# projetw2.net
KiCad netlist of a schematic drawn in EAGLE
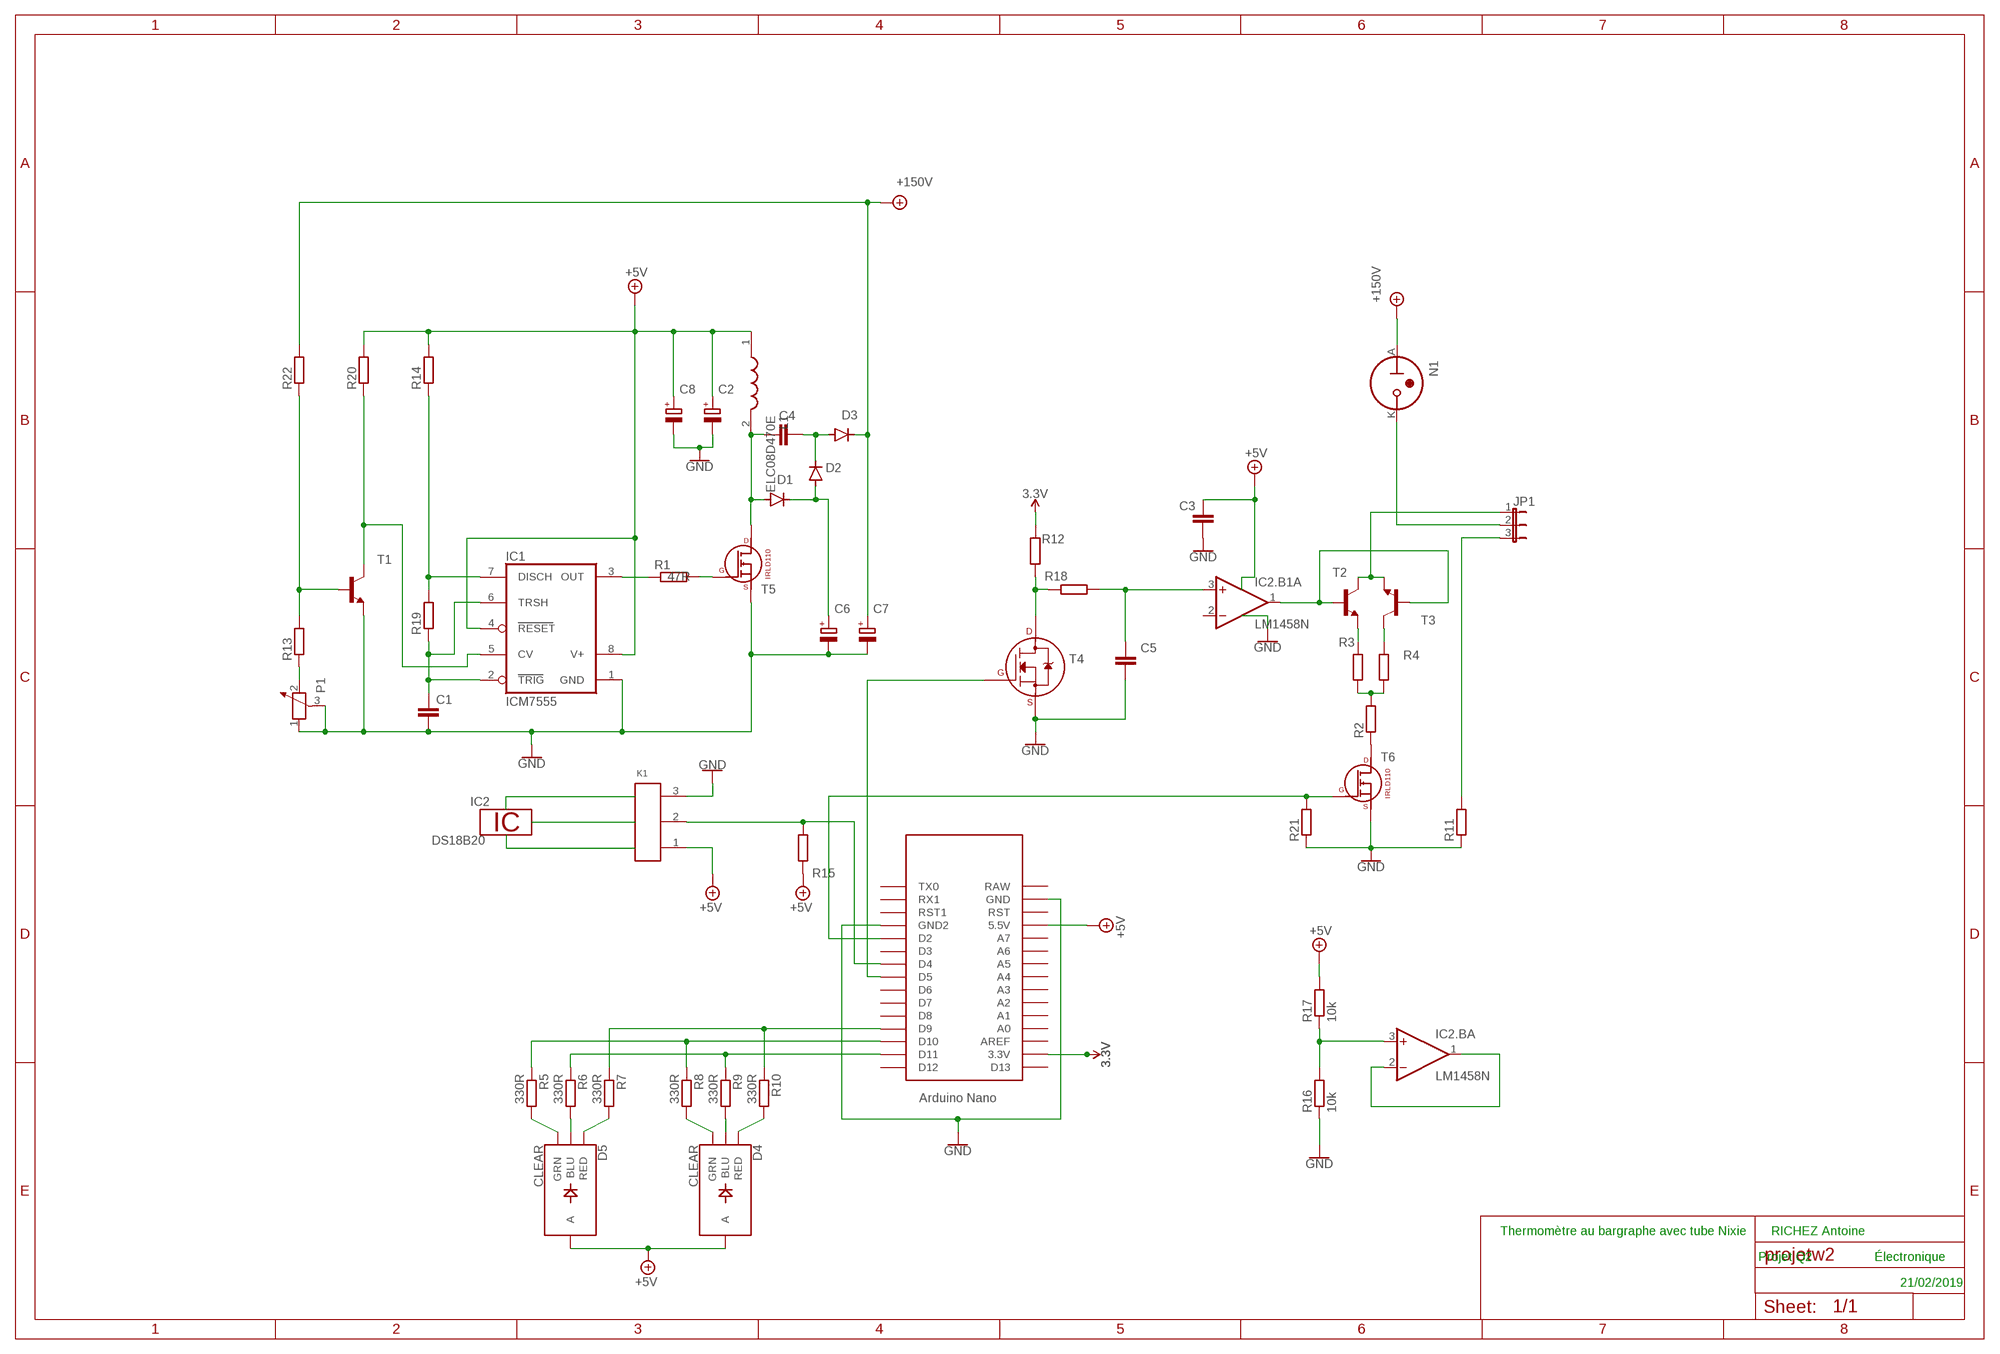
[diagram p0: schematic, sheet 1]

(export (version "E")
  (design (tool "Eeschema 10.0.6"))
  (components
    (comp (ref "C1")
      (value "C-EU025-024X044")
      (footprint "eagle-import:C025-024X044")
      (libsource (lib "eagle-import") (part "C-EU025-024X044"))
    )
    (comp (ref "C2")
      (value "CPOL-EUE2,5-6E")
      (footprint "eagle-import:E2,5-6E")
      (libsource (lib "eagle-import") (part "CPOL-EUE2,5-6E"))
    )
    (comp (ref "C3")
      (value "C-EU025-030X050")
      (footprint "eagle-import:C025-030X050")
      (libsource (lib "eagle-import") (part "C-EU025-030X050"))
    )
    (comp (ref "C4")
      (value "C-EU025-030X050")
      (footprint "eagle-import:C025-030X050")
      (libsource (lib "eagle-import") (part "C-EU025-030X050"))
    )
    (comp (ref "C5")
      (value "C-EU025-030X050")
      (footprint "eagle-import:C025-030X050")
      (libsource (lib "eagle-import") (part "C-EU025-030X050"))
    )
    (comp (ref "C6")
      (value "CPOL-EUE2,5-6E")
      (footprint "eagle-import:E2,5-6E")
      (libsource (lib "eagle-import") (part "CPOL-EUE2,5-6E"))
    )
    (comp (ref "C7")
      (value "CPOL-EUE2,5-6E")
      (footprint "eagle-import:E2,5-6E")
      (libsource (lib "eagle-import") (part "CPOL-EUE2,5-6E"))
    )
    (comp (ref "C8")
      (value "CPOL-EUE2,5-6E")
      (footprint "eagle-import:E2,5-6E")
      (libsource (lib "eagle-import") (part "CPOL-EUE2,5-6E"))
    )
    (comp (ref "D1")
      (value "MUR150RL")
      (footprint "eagle-import:DO41-10")
      (libsource (lib "eagle-import") (part "MUR150RL"))
    )
    (comp (ref "D2")
      (value "MUR150RL")
      (footprint "eagle-import:DO41-10")
      (libsource (lib "eagle-import") (part "MUR150RL"))
    )
    (comp (ref "D3")
      (value "MUR150RL")
      (footprint "eagle-import:DO41-10")
      (libsource (lib "eagle-import") (part "MUR150RL"))
    )
    (comp (ref "D4")
      (value "CLEAR")
      (footprint "eagle-import:LED-RGB-THRU")
      (libsource (lib "eagle-import") (part "LED-RGB-CACLEAR"))
    )
    (comp (ref "D5")
      (value "CLEAR")
      (footprint "eagle-import:LED-RGB-THRU")
      (libsource (lib "eagle-import") (part "LED-RGB-CACLEAR"))
    )
    (comp (ref "IC1")
      (value "ICM7555")
      (footprint "eagle-import:DIL08")
      (fields (field (name "MF") "MAXIM") (field (name "MPN") "ICM7555IPA+"))
      (libsource (lib "eagle-import") (part "ICM7555"))
    )
    (comp (ref "IC2")
      (value "DS18B20")
      (footprint "eagle-import:TO92-")
      (libsource (lib "eagle-import") (part "DS18B20"))
    )
    (comp (ref "IC2.B")
      (value "LM1458N")
      (footprint "eagle-import:DIL08")
      (libsource (lib "eagle-import") (part "1458NLM"))
    )
    (comp (ref "IC2.B1")
      (value "LM1458N")
      (footprint "eagle-import:DIL08")
      (libsource (lib "eagle-import") (part "1458NLM"))
    )
    (comp (ref "JP1")
      (value "JP2E")
      (footprint "eagle-import:JP2")
      (libsource (lib "eagle-import") (part "JP2E"))
    )
    (comp (ref "K1")
      (value "61900319521")
      (footprint "eagle-import:61900319521")
      (libsource (lib "eagle-import") (part "61900319521"))
    )
    (comp (ref "L1")
      (value "ELC08D470E")
      (footprint "eagle-import:ELC08D")
      (fields (field (name "MOUSER_PART_NUMBER") "2335178P"))
      (libsource (lib "eagle-import") (part "ELC08D470E"))
    )
    (comp (ref "N1")
      (value "IN-9")
      (footprint "eagle-import:IN-9")
      (libsource (lib "eagle-import") (part "IN-9"))
    )
    (comp (ref "P1")
      (value "POTENTIOMETER_PT-10")
      (footprint "eagle-import:PT-10")
      (libsource (lib "eagle-import") (part "POTENTIOMETER_PT-10"))
    )
    (comp (ref "R1")
      (value "47R")
      (footprint "eagle-import:0204_7")
      (libsource (lib "eagle-import") (part "R-EU_0204/7"))
    )
    (comp (ref "R2")
      (value "R-EU_0204/7")
      (footprint "eagle-import:0204_7")
      (libsource (lib "eagle-import") (part "R-EU_0204/7"))
    )
    (comp (ref "R3")
      (value "R-EU_0207/2V")
      (footprint "eagle-import:0207_2V")
      (libsource (lib "eagle-import") (part "R-EU_0207/2V"))
    )
    (comp (ref "R4")
      (value "R-EU_0207/2V")
      (footprint "eagle-import:0207_2V")
      (libsource (lib "eagle-import") (part "R-EU_0207/2V"))
    )
    (comp (ref "R5")
      (value "330R")
      (footprint "eagle-import:0204V")
      (libsource (lib "eagle-import") (part "R-EU_0204/2V"))
    )
    (comp (ref "R6")
      (value "330R")
      (footprint "eagle-import:0204V")
      (libsource (lib "eagle-import") (part "R-EU_0204/2V"))
    )
    (comp (ref "R7")
      (value "330R")
      (footprint "eagle-import:0204V")
      (libsource (lib "eagle-import") (part "R-EU_0204/2V"))
    )
    (comp (ref "R8")
      (value "330R")
      (footprint "eagle-import:0204V")
      (libsource (lib "eagle-import") (part "R-EU_0204/2V"))
    )
    (comp (ref "R9")
      (value "330R")
      (footprint "eagle-import:0204V")
      (libsource (lib "eagle-import") (part "R-EU_0204/2V"))
    )
    (comp (ref "R10")
      (value "330R")
      (footprint "eagle-import:0204V")
      (libsource (lib "eagle-import") (part "R-EU_0204/2V"))
    )
    (comp (ref "R11")
      (value "R-EU_0204/7")
      (footprint "eagle-import:0204_7")
      (libsource (lib "eagle-import") (part "R-EU_0204/7"))
    )
    (comp (ref "R12")
      (value "R-EU_0207/2V")
      (footprint "eagle-import:0207_2V")
      (libsource (lib "eagle-import") (part "R-EU_0207/2V"))
    )
    (comp (ref "R13")
      (value "R-EU_0207/2V")
      (footprint "eagle-import:0207_2V")
      (libsource (lib "eagle-import") (part "R-EU_0207/2V"))
    )
    (comp (ref "R14")
      (value "R-EU_0207/2V")
      (footprint "eagle-import:0207_2V")
      (libsource (lib "eagle-import") (part "R-EU_0207/2V"))
    )
    (comp (ref "R15")
      (value "R-EU_0204/7")
      (footprint "eagle-import:0204_7")
      (libsource (lib "eagle-import") (part "R-EU_0204/7"))
    )
    (comp (ref "R16")
      (value "10k")
      (footprint "eagle-import:0204V")
      (libsource (lib "eagle-import") (part "R-EU_0204/2V"))
    )
    (comp (ref "R17")
      (value "10k")
      (footprint "eagle-import:0204V")
      (libsource (lib "eagle-import") (part "R-EU_0204/2V"))
    )
    (comp (ref "R18")
      (value "R-EU_0207/2V")
      (footprint "eagle-import:0207_2V")
      (libsource (lib "eagle-import") (part "R-EU_0207/2V"))
    )
    (comp (ref "R19")
      (value "R-EU_0207/2V")
      (footprint "eagle-import:0207_2V")
      (libsource (lib "eagle-import") (part "R-EU_0207/2V"))
    )
    (comp (ref "R20")
      (value "R-EU_0207/2V")
      (footprint "eagle-import:0207_2V")
      (libsource (lib "eagle-import") (part "R-EU_0207/2V"))
    )
    (comp (ref "R21")
      (value "R-EU_0204/7")
      (footprint "eagle-import:0204_7")
      (libsource (lib "eagle-import") (part "R-EU_0204/7"))
    )
    (comp (ref "R22")
      (value "R-EU_0207/2V")
      (footprint "eagle-import:0207_2V")
      (libsource (lib "eagle-import") (part "R-EU_0207/2V"))
    )
    (comp (ref "T1")
      (value "BC547B-NPN-TO92-CBE")
      (footprint "eagle-import:TO92-CBE")
      (libsource (lib "eagle-import") (part "-NPN-TO92-CBEBC547B"))
    )
    (comp (ref "T2")
      (value "MPSA42-NPN-TO92-EBC")
      (footprint "eagle-import:TO92-EBC")
      (libsource (lib "eagle-import") (part "-NPN-TO92-EBCMPSA42"))
    )
    (comp (ref "T3")
      (value "MPSA42-NPN-TO92-EBC")
      (footprint "eagle-import:TO92-EBC")
      (libsource (lib "eagle-import") (part "-NPN-TO92-EBCMPSA42"))
    )
    (comp (ref "T4")
      (value "2N7000_TO92")
      (footprint "eagle-import:TO-92")
      (libsource (lib "eagle-import") (part "2N700_TO920"))
    )
    (comp (ref "T5")
      (value "-IRLD")
      (footprint "eagle-import:IRLD110")
      (libsource (lib "eagle-import") (part "-IRLD"))
    )
    (comp (ref "T6")
      (value "-IRLD")
      (footprint "eagle-import:IRLD110")
      (libsource (lib "eagle-import") (part "-IRLD"))
    )
    (comp (ref "U$1")
      (value "NANO")
      (footprint "eagle-import:NANO")
      (libsource (lib "eagle-import") (part "NANO"))
    )
  )
  (nets
    (net (code "1") (name "+150V") (class "Default")
      (node (ref "C2") (pin "+") (pinfunction "+_+") (pintype "passive"))
      (node (ref "C3") (pin "1") (pinfunction "1_1") (pintype "passive"))
      (node (ref "C7") (pin "+") (pinfunction "+_+") (pintype "passive"))
      (node (ref "C8") (pin "+") (pinfunction "+_+") (pintype "passive"))
      (node (ref "D3") (pin "C") (pinfunction "C_C") (pintype "passive"))
      (node (ref "D4") (pin "2") (pinfunction "A_2") (pintype "bidirectional"))
      (node (ref "D5") (pin "2") (pinfunction "A_2") (pintype "bidirectional"))
      (node (ref "IC1") (pin "4") (pinfunction "RESET_4") (pintype "input"))
      (node (ref "IC1") (pin "8") (pinfunction "V+_8") (pintype "power_in"))
      (node (ref "K1") (pin "1") (pinfunction "3_1") (pintype "passive"))
      (node (ref "L1") (pin "1") (pinfunction "1_1") (pintype "bidirectional"))
      (node (ref "N1") (pin "A") (pinfunction "A_A") (pintype "bidirectional"))
      (node (ref "R14") (pin "2") (pinfunction "2_2") (pintype "passive"))
      (node (ref "R15") (pin "1") (pinfunction "1_1") (pintype "passive"))
      (node (ref "R17") (pin "2") (pinfunction "2_2") (pintype "passive"))
      (node (ref "R20") (pin "2") (pinfunction "2_2") (pintype "passive"))
      (node (ref "R22") (pin "2") (pinfunction "2_2") (pintype "passive"))
      (node (ref "U$1") (pin "5V") (pinfunction "5.5V_5V") (pintype "bidirectional"))
    )
    (net (code "2") (name "3.3V") (class "Default")
      (node (ref "R12") (pin "1") (pinfunction "1_1") (pintype "passive"))
      (node (ref "U$1") (pin "3.3V") (pinfunction "3.3V_3.3V") (pintype "bidirectional"))
    )
    (net (code "3") (name "GND") (class "Default")
      (node (ref "C1") (pin "2") (pinfunction "2_2") (pintype "passive"))
      (node (ref "C2") (pin "-") (pinfunction "-_-") (pintype "passive"))
      (node (ref "C3") (pin "2") (pinfunction "2_2") (pintype "passive"))
      (node (ref "C5") (pin "2") (pinfunction "2_2") (pintype "passive"))
      (node (ref "C6") (pin "-") (pinfunction "-_-") (pintype "passive"))
      (node (ref "C7") (pin "-") (pinfunction "-_-") (pintype "passive"))
      (node (ref "C8") (pin "-") (pinfunction "-_-") (pintype "passive"))
      (node (ref "IC1") (pin "1") (pinfunction "GND_1") (pintype "power_in"))
      (node (ref "K1") (pin "3") (pinfunction "1_3") (pintype "passive"))
      (node (ref "P1") (pin "1") (pinfunction "1_1") (pintype "passive"))
      (node (ref "P1") (pin "3") (pinfunction "3_3") (pintype "passive"))
      (node (ref "R11") (pin "1") (pinfunction "1_1") (pintype "passive"))
      (node (ref "R16") (pin "1") (pinfunction "1_1") (pintype "passive"))
      (node (ref "R21") (pin "1") (pinfunction "1_1") (pintype "passive"))
      (node (ref "T1") (pin "E") (pinfunction "E_E") (pintype "passive"))
      (node (ref "T4") (pin "1") (pinfunction "S_1") (pintype "bidirectional"))
      (node (ref "T5") (pin "SOURCE") (pinfunction "SOURCE_SOURCE") (pintype "passive"))
      (node (ref "T6") (pin "SOURCE") (pinfunction "SOURCE_SOURCE") (pintype "passive"))
      (node (ref "U$1") (pin "GND") (pinfunction "GND_GND") (pintype "bidirectional"))
      (node (ref "U$1") (pin "GND1") (pinfunction "GND2_GND1") (pintype "bidirectional"))
    )
    (net (code "4") (name "Net-(C4-Pad2)") (class "Default")
      (node (ref "C4") (pin "2") (pinfunction "2_2") (pintype "passive"))
      (node (ref "D2") (pin "C") (pinfunction "C_C") (pintype "passive"))
      (node (ref "D3") (pin "A") (pinfunction "A_A") (pintype "passive"))
    )
    (net (code "5") (name "Net-(C6-Pad+)") (class "Default")
      (node (ref "C6") (pin "+") (pinfunction "+_+") (pintype "passive"))
      (node (ref "D1") (pin "C") (pinfunction "C_C") (pintype "passive"))
      (node (ref "D2") (pin "A") (pinfunction "A_A") (pintype "passive"))
    )
    (net (code "6") (name "Net-(D4-BLU)") (class "Default")
      (node (ref "D4") (pin "4") (pinfunction "BLU_4") (pintype "bidirectional"))
      (node (ref "R9") (pin "2") (pinfunction "2_2") (pintype "passive"))
    )
    (net (code "7") (name "Net-(D4-GRN)") (class "Default")
      (node (ref "D4") (pin "3") (pinfunction "GRN_3") (pintype "bidirectional"))
      (node (ref "R8") (pin "2") (pinfunction "2_2") (pintype "passive"))
    )
    (net (code "8") (name "Net-(D4-RED)") (class "Default")
      (node (ref "D4") (pin "1") (pinfunction "RED_1") (pintype "bidirectional"))
      (node (ref "R10") (pin "2") (pinfunction "2_2") (pintype "passive"))
    )
    (net (code "9") (name "Net-(D5-BLU)") (class "Default")
      (node (ref "D5") (pin "4") (pinfunction "BLU_4") (pintype "bidirectional"))
      (node (ref "R6") (pin "2") (pinfunction "2_2") (pintype "passive"))
    )
    (net (code "10") (name "Net-(D5-GRN)") (class "Default")
      (node (ref "D5") (pin "3") (pinfunction "GRN_3") (pintype "bidirectional"))
      (node (ref "R5") (pin "2") (pinfunction "2_2") (pintype "passive"))
    )
    (net (code "11") (name "Net-(D5-RED)") (class "Default")
      (node (ref "D5") (pin "1") (pinfunction "RED_1") (pintype "bidirectional"))
      (node (ref "R7") (pin "2") (pinfunction "2_2") (pintype "passive"))
    )
    (net (code "12") (name "Net-(IC1-CV)") (class "Default")
      (node (ref "IC1") (pin "5") (pinfunction "CV_5") (pintype "passive"))
      (node (ref "R20") (pin "1") (pinfunction "1_1") (pintype "passive"))
      (node (ref "T1") (pin "C") (pinfunction "C_C") (pintype "passive"))
    )
    (net (code "13") (name "Net-(IC1-DISCH)") (class "Default")
      (node (ref "IC1") (pin "7") (pinfunction "DISCH_7") (pintype "input"))
      (node (ref "R14") (pin "1") (pinfunction "1_1") (pintype "passive"))
      (node (ref "R19") (pin "2") (pinfunction "2_2") (pintype "passive"))
    )
    (net (code "14") (name "Net-(IC1-OUT)") (class "Default")
      (node (ref "IC1") (pin "3") (pinfunction "OUT_3") (pintype "output"))
      (node (ref "R1") (pin "1") (pinfunction "1_1") (pintype "passive"))
    )
    (net (code "15") (name "Net-(IC1-TRIG)") (class "Default")
      (node (ref "C1") (pin "1") (pinfunction "1_1") (pintype "passive"))
      (node (ref "IC1") (pin "2") (pinfunction "TRIG_2") (pintype "bidirectional"))
      (node (ref "IC1") (pin "6") (pinfunction "TRSH_6") (pintype "input"))
      (node (ref "R19") (pin "1") (pinfunction "1_1") (pintype "passive"))
    )
    (net (code "16") (name "Net-(IC2.B1A-+IN)") (class "Default")
      (node (ref "C5") (pin "1") (pinfunction "1_1") (pintype "passive"))
      (node (ref "IC2.B1") (pin "3") (pinfunction "+IN_3") (pintype "input"))
      (node (ref "R18") (pin "1") (pinfunction "1_1") (pintype "passive"))
    )
    (net (code "17") (name "Net-(IC2.B1A-OUT)") (class "Default")
      (node (ref "IC2.B1") (pin "1") (pinfunction "OUT_1") (pintype "output"))
      (node (ref "T2") (pin "B") (pinfunction "B_B") (pintype "passive"))
      (node (ref "T3") (pin "B") (pinfunction "B_B") (pintype "passive"))
    )
    (net (code "18") (name "Net-(IC2.BA-+IN)") (class "Default")
      (node (ref "IC2.B") (pin "3") (pinfunction "+IN_3") (pintype "input"))
      (node (ref "R16") (pin "2") (pinfunction "2_2") (pintype "passive"))
      (node (ref "R17") (pin "1") (pinfunction "1_1") (pintype "passive"))
    )
    (net (code "19") (name "Net-(IC2.BA--IN)") (class "Default")
      (node (ref "IC2.B") (pin "1") (pinfunction "OUT_1") (pintype "output"))
      (node (ref "IC2.B") (pin "2") (pinfunction "-IN_2") (pintype "input"))
    )
    (net (code "20") (name "Net-(JP1-Pad1)") (class "Default")
      (node (ref "JP1") (pin "1") (pinfunction "1_1") (pintype "passive"))
      (node (ref "T2") (pin "C") (pinfunction "C_C") (pintype "passive"))
      (node (ref "T3") (pin "E") (pinfunction "E_E") (pintype "passive"))
    )
    (net (code "21") (name "Net-(JP1-Pad2)") (class "Default")
      (node (ref "JP1") (pin "2") (pinfunction "2_2") (pintype "passive"))
      (node (ref "N1") (pin "K") (pinfunction "K_K") (pintype "bidirectional"))
    )
    (net (code "22") (name "Net-(JP1-Pad3)") (class "Default")
      (node (ref "JP1") (pin "3") (pinfunction "3_3") (pintype "passive"))
      (node (ref "R11") (pin "2") (pinfunction "2_2") (pintype "passive"))
    )
    (net (code "23") (name "Net-(K1-Pad2)") (class "Default")
      (node (ref "K1") (pin "2") (pinfunction "2_2") (pintype "passive"))
      (node (ref "R15") (pin "2") (pinfunction "2_2") (pintype "passive"))
      (node (ref "U$1") (pin "D4") (pinfunction "D4_D4") (pintype "bidirectional"))
    )
    (net (code "24") (name "Net-(P1-Pad2)") (class "Default")
      (node (ref "P1") (pin "2") (pinfunction "2_2") (pintype "passive"))
      (node (ref "R13") (pin "1") (pinfunction "1_1") (pintype "passive"))
    )
    (net (code "25") (name "Net-(R1-Pad2)") (class "Default")
      (node (ref "R1") (pin "2") (pinfunction "2_2") (pintype "passive"))
      (node (ref "T5") (pin "GATE") (pinfunction "GATE_GATE") (pintype "passive"))
    )
    (net (code "26") (name "Net-(R2-Pad2)") (class "Default")
      (node (ref "R2") (pin "2") (pinfunction "2_2") (pintype "passive"))
      (node (ref "R3") (pin "2") (pinfunction "2_2") (pintype "passive"))
      (node (ref "R4") (pin "2") (pinfunction "2_2") (pintype "passive"))
    )
    (net (code "27") (name "Net-(R3-Pad1)") (class "Default")
      (node (ref "R3") (pin "1") (pinfunction "1_1") (pintype "passive"))
      (node (ref "T2") (pin "E") (pinfunction "E_E") (pintype "passive"))
    )
    (net (code "28") (name "Net-(R4-Pad1)") (class "Default")
      (node (ref "R4") (pin "1") (pinfunction "1_1") (pintype "passive"))
      (node (ref "T3") (pin "C") (pinfunction "C_C") (pintype "passive"))
    )
    (net (code "29") (name "Net-(R5-Pad1)") (class "Default")
      (node (ref "R5") (pin "1") (pinfunction "1_1") (pintype "passive"))
      (node (ref "R8") (pin "1") (pinfunction "1_1") (pintype "passive"))
      (node (ref "U$1") (pin "D10") (pinfunction "D10_D10") (pintype "bidirectional"))
    )
    (net (code "30") (name "Net-(R6-Pad1)") (class "Default")
      (node (ref "R6") (pin "1") (pinfunction "1_1") (pintype "passive"))
      (node (ref "R9") (pin "1") (pinfunction "1_1") (pintype "passive"))
      (node (ref "U$1") (pin "D11") (pinfunction "D11_D11") (pintype "bidirectional"))
    )
    (net (code "31") (name "Net-(R10-Pad1)") (class "Default")
      (node (ref "R10") (pin "1") (pinfunction "1_1") (pintype "passive"))
      (node (ref "R7") (pin "1") (pinfunction "1_1") (pintype "passive"))
      (node (ref "U$1") (pin "D9") (pinfunction "D9_D9") (pintype "bidirectional"))
    )
    (net (code "32") (name "Net-(R13-Pad2)") (class "Default")
      (node (ref "R13") (pin "2") (pinfunction "2_2") (pintype "passive"))
      (node (ref "R22") (pin "1") (pinfunction "1_1") (pintype "passive"))
      (node (ref "T1") (pin "B") (pinfunction "B_B") (pintype "passive"))
    )
    (net (code "33") (name "Net-(R21-Pad2)") (class "Default")
      (node (ref "R21") (pin "2") (pinfunction "2_2") (pintype "passive"))
      (node (ref "T6") (pin "GATE") (pinfunction "GATE_GATE") (pintype "passive"))
      (node (ref "U$1") (pin "D2") (pinfunction "D2_D2") (pintype "bidirectional"))
    )
    (net (code "34") (name "Net-(T4-D)") (class "Default")
      (node (ref "R12") (pin "2") (pinfunction "2_2") (pintype "passive"))
      (node (ref "R18") (pin "2") (pinfunction "2_2") (pintype "passive"))
      (node (ref "T4") (pin "3") (pinfunction "D_3") (pintype "bidirectional"))
    )
    (net (code "35") (name "Net-(T4-G)") (class "Default")
      (node (ref "T4") (pin "2") (pinfunction "G_2") (pintype "tri_state"))
      (node (ref "U$1") (pin "D5") (pinfunction "D5_D5") (pintype "bidirectional"))
    )
    (net (code "36") (name "Net-(T5-DRAIN)") (class "Default")
      (node (ref "C4") (pin "1") (pinfunction "1_1") (pintype "passive"))
      (node (ref "D1") (pin "A") (pinfunction "A_A") (pintype "passive"))
      (node (ref "L1") (pin "2") (pinfunction "2_2") (pintype "bidirectional"))
      (node (ref "T5") (pin "DRAIN1") (pinfunction "DRAIN_DRAIN1") (pintype "passive"))
    )
    (net (code "37") (name "Net-(T6-DRAIN)") (class "Default")
      (node (ref "R2") (pin "1") (pinfunction "1_1") (pintype "passive"))
      (node (ref "T6") (pin "DRAIN1") (pinfunction "DRAIN_DRAIN1") (pintype "passive"))
    )
    (net (code "38") (name "unconnected-(IC2.B1A--IN-Pad2)") (class "Default")
      (node (ref "IC2.B1") (pin "2") (pinfunction "-IN_2") (pintype "input"))
    )
    (net (code "39") (name "unconnected-(U$1-PadA0)") (class "Default")
      (node (ref "U$1") (pin "A0") (pinfunction "A0_A0") (pintype "bidirectional"))
    )
    (net (code "40") (name "unconnected-(U$1-PadA1)") (class "Default")
      (node (ref "U$1") (pin "A1") (pinfunction "A1_A1") (pintype "bidirectional"))
    )
    (net (code "41") (name "unconnected-(U$1-PadA2)") (class "Default")
      (node (ref "U$1") (pin "A2") (pinfunction "A2_A2") (pintype "bidirectional"))
    )
    (net (code "42") (name "unconnected-(U$1-PadA3)") (class "Default")
      (node (ref "U$1") (pin "A3") (pinfunction "A3_A3") (pintype "bidirectional"))
    )
    (net (code "43") (name "unconnected-(U$1-PadA4)") (class "Default")
      (node (ref "U$1") (pin "A4") (pinfunction "A4_A4") (pintype "bidirectional"))
    )
    (net (code "44") (name "unconnected-(U$1-PadA5)") (class "Default")
      (node (ref "U$1") (pin "A5") (pinfunction "A5_A5") (pintype "bidirectional"))
    )
    (net (code "45") (name "unconnected-(U$1-PadA6)") (class "Default")
      (node (ref "U$1") (pin "A6") (pinfunction "A6_A6") (pintype "bidirectional"))
    )
    (net (code "46") (name "unconnected-(U$1-PadA7)") (class "Default")
      (node (ref "U$1") (pin "A7") (pinfunction "A7_A7") (pintype "bidirectional"))
    )
    (net (code "47") (name "unconnected-(U$1-PadAREF)") (class "Default")
      (node (ref "U$1") (pin "AREF") (pinfunction "AREF_AREF") (pintype "bidirectional"))
    )
    (net (code "48") (name "unconnected-(U$1-PadD3)") (class "Default")
      (node (ref "U$1") (pin "D3") (pinfunction "D3_D3") (pintype "bidirectional"))
    )
    (net (code "49") (name "unconnected-(U$1-PadD6)") (class "Default")
      (node (ref "U$1") (pin "D6") (pinfunction "D6_D6") (pintype "bidirectional"))
    )
    (net (code "50") (name "unconnected-(U$1-PadD7)") (class "Default")
      (node (ref "U$1") (pin "D7") (pinfunction "D7_D7") (pintype "bidirectional"))
    )
    (net (code "51") (name "unconnected-(U$1-PadD8)") (class "Default")
      (node (ref "U$1") (pin "D8") (pinfunction "D8_D8") (pintype "bidirectional"))
    )
    (net (code "52") (name "unconnected-(U$1-PadD12)") (class "Default")
      (node (ref "U$1") (pin "D12") (pinfunction "D12_D12") (pintype "bidirectional"))
    )
    (net (code "53") (name "unconnected-(U$1-PadD13)") (class "Default")
      (node (ref "U$1") (pin "D13") (pinfunction "D13_D13") (pintype "bidirectional"))
    )
    (net (code "54") (name "unconnected-(U$1-PadICSP1)") (class "Default")
      (node (ref "U$1") (pin "ICSP1") (pinfunction "ICSP1_ICSP1") (pintype "bidirectional"))
    )
    (net (code "55") (name "unconnected-(U$1-PadICSP2)") (class "Default")
      (node (ref "U$1") (pin "ICSP2") (pinfunction "ICSP2_ICSP2") (pintype "bidirectional"))
    )
    (net (code "56") (name "unconnected-(U$1-PadICSP3)") (class "Default")
      (node (ref "U$1") (pin "ICSP3") (pinfunction "ICSP3_ICSP3") (pintype "bidirectional"))
    )
    (net (code "57") (name "unconnected-(U$1-PadICSP4)") (class "Default")
      (node (ref "U$1") (pin "ICSP4") (pinfunction "ICSP4_ICSP4") (pintype "bidirectional"))
    )
    (net (code "58") (name "unconnected-(U$1-PadICSP5)") (class "Default")
      (node (ref "U$1") (pin "ICSP5") (pinfunction "ICSP5_ICSP5") (pintype "bidirectional"))
    )
    (net (code "59") (name "unconnected-(U$1-PadICSP6)") (class "Default")
      (node (ref "U$1") (pin "ICSP6") (pinfunction "ICSP6_ICSP6") (pintype "bidirectional"))
    )
    (net (code "60") (name "unconnected-(U$1-PadRAW)") (class "Default")
      (node (ref "U$1") (pin "RAW") (pinfunction "RAW_RAW") (pintype "bidirectional"))
    )
    (net (code "61") (name "unconnected-(U$1-PadRST)") (class "Default")
      (node (ref "U$1") (pin "RST") (pinfunction "RST_RST") (pintype "bidirectional"))
    )
    (net (code "62") (name "unconnected-(U$1-PadRST1)") (class "Default")
      (node (ref "U$1") (pin "RST1") (pinfunction "RST1_RST1") (pintype "bidirectional"))
    )
    (net (code "63") (name "unconnected-(U$1-PadRX1)") (class "Default")
      (node (ref "U$1") (pin "RX1") (pinfunction "RX1_RX1") (pintype "bidirectional"))
    )
    (net (code "64") (name "unconnected-(U$1-PadTX0)") (class "Default")
      (node (ref "U$1") (pin "TX0") (pinfunction "TX0_TX0") (pintype "bidirectional"))
    )
  )
)
